# 08_-_MMC_SLOT.net
KiCad netlist of a schematic drawn in Altium Designer
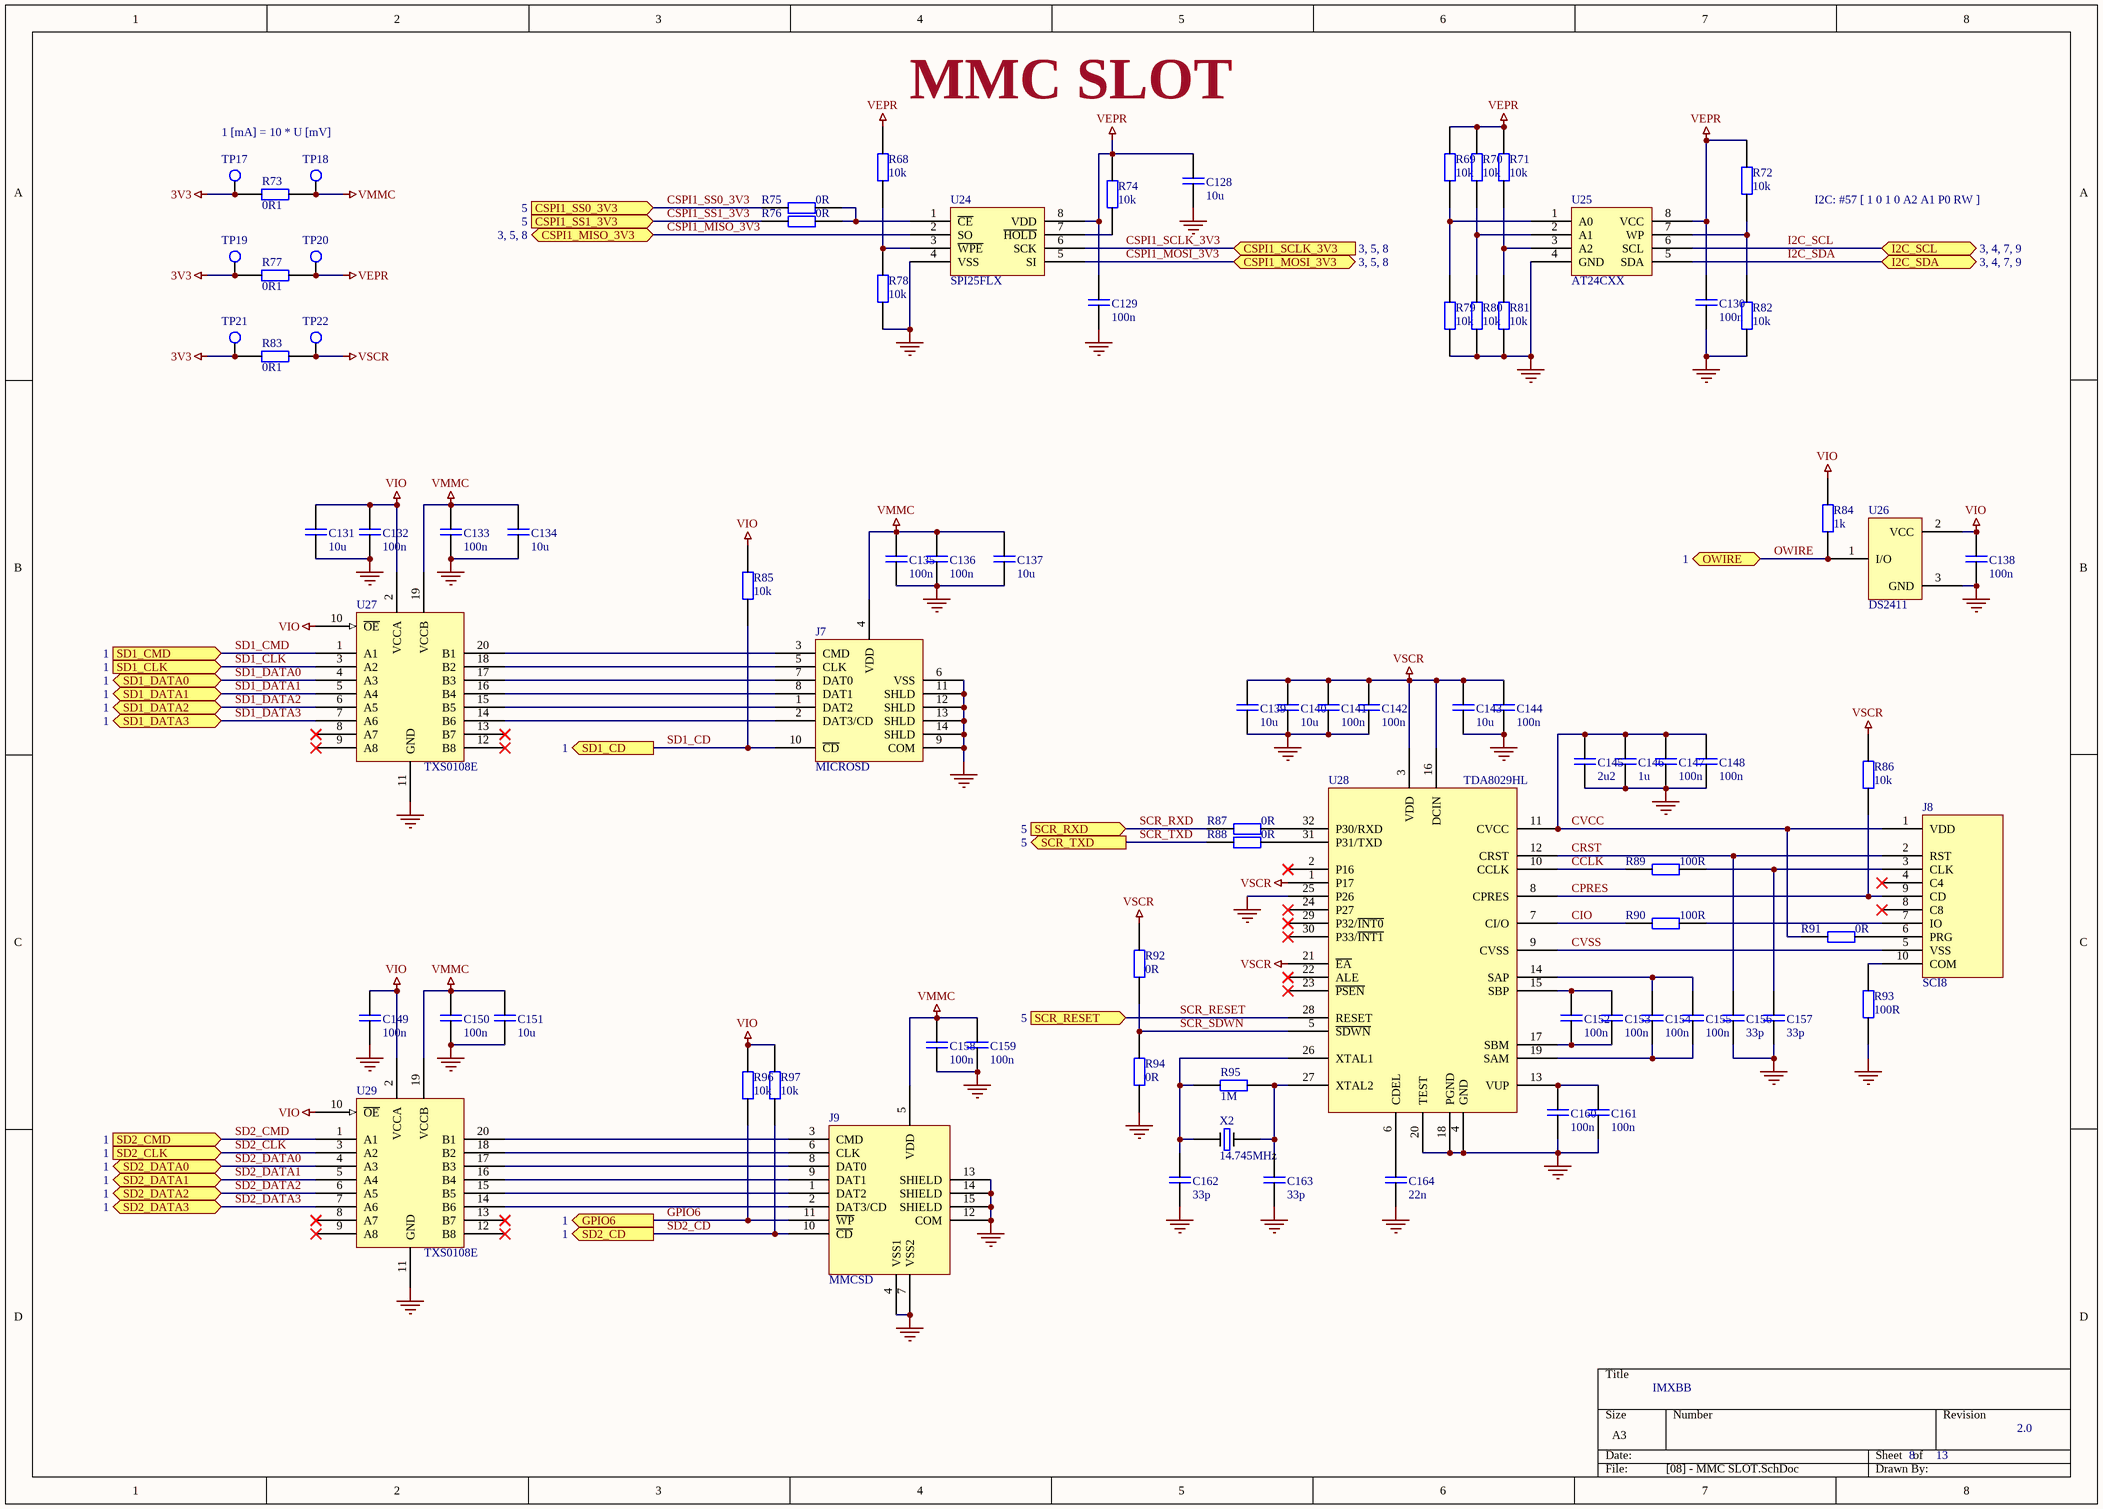
[diagram p0: [08] - MMC SLOT.SchDoc]

(export (version "E")
  (design (tool "Eeschema 10.0.6"))
  (components
    (comp (ref "C128") (value "10u") (footprint "0805") (libsource (lib "imxbb") (part "C")))
    (comp (ref "C129") (value "100n") (footprint "0603") (libsource (lib "imxbb") (part "C")))
    (comp (ref "C130") (value "100n") (footprint "0603") (libsource (lib "imxbb") (part "C")))
    (comp (ref "C131") (value "10u") (footprint "0805") (libsource (lib "imxbb") (part "C")))
    (comp (ref "C132") (value "100n") (footprint "0603") (libsource (lib "imxbb") (part "C")))
    (comp (ref "C133") (value "100n") (footprint "0603") (libsource (lib "imxbb") (part "C")))
    (comp (ref "C134") (value "10u") (footprint "0805") (libsource (lib "imxbb") (part "C")))
    (comp (ref "C135") (value "100n") (footprint "0603") (libsource (lib "imxbb") (part "C")))
    (comp (ref "C136") (value "100n") (footprint "0603") (libsource (lib "imxbb") (part "C")))
    (comp (ref "C137") (value "10u") (footprint "0805") (libsource (lib "imxbb") (part "C")))
    (comp (ref "C138") (value "100n") (footprint "0603") (libsource (lib "imxbb") (part "C")))
    (comp (ref "C139") (value "10u") (footprint "0805") (libsource (lib "imxbb") (part "C")))
    (comp (ref "C140") (value "10u") (footprint "0805") (libsource (lib "imxbb") (part "C")))
    (comp (ref "C141") (value "100n") (footprint "0603") (libsource (lib "imxbb") (part "C")))
    (comp (ref "C142") (value "100n") (footprint "0603") (libsource (lib "imxbb") (part "C")))
    (comp (ref "C143") (value "10u") (footprint "0805") (libsource (lib "imxbb") (part "C")))
    (comp (ref "C144") (value "100n") (footprint "0603") (libsource (lib "imxbb") (part "C")))
    (comp (ref "C145") (value "2u2") (footprint "0603") (libsource (lib "imxbb") (part "C")))
    (comp (ref "C146") (value "1u") (footprint "0603") (libsource (lib "imxbb") (part "C")))
    (comp (ref "C147") (value "100n") (footprint "0603") (libsource (lib "imxbb") (part "C")))
    (comp (ref "C148") (value "100n") (footprint "0603") (libsource (lib "imxbb") (part "C")))
    (comp (ref "C149") (value "100n") (footprint "0603") (libsource (lib "imxbb") (part "C")))
    (comp (ref "C150") (value "100n") (footprint "0603") (libsource (lib "imxbb") (part "C")))
    (comp (ref "C151") (value "10u") (footprint "0805") (libsource (lib "imxbb") (part "C")))
    (comp (ref "C152") (value "100n") (footprint "0603") (libsource (lib "imxbb") (part "C")))
    (comp (ref "C153") (value "100n") (footprint "0603") (libsource (lib "imxbb") (part "C")))
    (comp (ref "C154") (value "100n") (footprint "0603") (libsource (lib "imxbb") (part "C")))
    (comp (ref "C155") (value "100n") (footprint "0603") (libsource (lib "imxbb") (part "C")))
    (comp (ref "C156") (value "33p") (footprint "0603") (libsource (lib "imxbb") (part "C")))
    (comp (ref "C157") (value "33p") (footprint "0603") (libsource (lib "imxbb") (part "C")))
    (comp (ref "C158") (value "100n") (footprint "0603") (libsource (lib "imxbb") (part "C")))
    (comp (ref "C159") (value "100n") (footprint "0603") (libsource (lib "imxbb") (part "C")))
    (comp (ref "C160") (value "100n") (footprint "0603") (libsource (lib "imxbb") (part "C")))
    (comp (ref "C161") (value "100n") (footprint "0603") (libsource (lib "imxbb") (part "C")))
    (comp (ref "C162") (value "33p") (footprint "0603") (libsource (lib "imxbb") (part "C")))
    (comp (ref "C163") (value "33p") (footprint "0603") (libsource (lib "imxbb") (part "C")))
    (comp (ref "C164") (value "22n") (footprint "0603") (libsource (lib "imxbb") (part "C")))
    (comp (ref "J7") (value "MICROSD") (footprint "uSD10") (libsource (lib "imxbb") (part "MICROSD")))
    (comp (ref "J8") (value "SCI8") (footprint "SCI8F") (libsource (lib "imxbb") (part "SCI8")))
    (comp (ref "J9") (value "MMCSD") (footprint "SDCMF-109") (libsource (lib "imxbb") (part "MMCSD")))
    (comp (ref "R68") (value "10k") (footprint "0603") (libsource (lib "imxbb") (part "R")))
    (comp (ref "R69") (value "10k") (footprint "0603") (libsource (lib "imxbb") (part "R")))
    (comp (ref "R70") (value "10k") (footprint "0603") (libsource (lib "imxbb") (part "R")))
    (comp (ref "R71") (value "10k") (footprint "0603") (libsource (lib "imxbb") (part "R")))
    (comp (ref "R72") (value "10k") (footprint "0603") (libsource (lib "imxbb") (part "R")))
    (comp (ref "R73") (value "0R1") (footprint "0603") (libsource (lib "") (part "R_4")))
    (comp (ref "R74") (value "10k") (footprint "0603") (libsource (lib "imxbb") (part "R")))
    (comp (ref "R75") (value "0R") (footprint "0603") (libsource (lib "") (part "R_1")))
    (comp (ref "R76") (value "0R") (footprint "0603") (libsource (lib "") (part "R_1")))
    (comp (ref "R77") (value "0R1") (footprint "0603") (libsource (lib "") (part "R_4")))
    (comp (ref "R78") (value "10k") (footprint "0603") (libsource (lib "imxbb") (part "R")))
    (comp (ref "R79") (value "10k") (footprint "0603") (libsource (lib "imxbb") (part "R")))
    (comp (ref "R80") (value "10k") (footprint "0603") (libsource (lib "imxbb") (part "R")))
    (comp (ref "R81") (value "10k") (footprint "0603") (libsource (lib "imxbb") (part "R")))
    (comp (ref "R82") (value "10k") (footprint "0603") (libsource (lib "imxbb") (part "R")))
    (comp (ref "R83") (value "0R1") (footprint "0603") (libsource (lib "") (part "R_4")))
    (comp (ref "R84") (value "1k") (footprint "0603") (libsource (lib "imxbb") (part "R")))
    (comp (ref "R85") (value "10k") (footprint "0603") (libsource (lib "imxbb") (part "R")))
    (comp (ref "R86") (value "10k") (footprint "0603") (libsource (lib "") (part "R_3")))
    (comp (ref "R87") (value "0R") (footprint "0603") (libsource (lib "") (part "R_1")))
    (comp (ref "R88") (value "0R") (footprint "0603") (libsource (lib "") (part "R_1")))
    (comp (ref "R89") (value "100R") (footprint "0603") (libsource (lib "") (part "R_1")))
    (comp (ref "R90") (value "100R") (footprint "0603") (libsource (lib "") (part "R_1")))
    (comp (ref "R91") (value "0R") (footprint "0603") (libsource (lib "") (part "R_1")))
    (comp (ref "R92") (value "0R") (footprint "0603") (libsource (lib "") (part "R_3")))
    (comp (ref "R93") (value "100R") (footprint "0603") (libsource (lib "") (part "R_3")))
    (comp (ref "R94") (value "0R") (footprint "0603") (libsource (lib "") (part "R_3")))
    (comp (ref "R95") (value "1M") (footprint "0603") (libsource (lib "") (part "R_2")))
    (comp (ref "R96") (value "10k") (footprint "0603") (libsource (lib "imxbb") (part "R")))
    (comp (ref "R97") (value "10k") (footprint "0603") (libsource (lib "imxbb") (part "R")))
    (comp (ref "TP17")
      (value "TESTPOINT")
      (footprint "TESTPOINT_2mm")
      (description "Testpoint pad")
      (libsource (lib "imxbb") (part "TESTPOINT"))
    )
    (comp (ref "TP18")
      (value "TESTPOINT")
      (footprint "TESTPOINT_2mm")
      (description "Testpoint pad")
      (libsource (lib "imxbb") (part "TESTPOINT"))
    )
    (comp (ref "TP19")
      (value "TESTPOINT")
      (footprint "TESTPOINT_2mm")
      (description "Testpoint pad")
      (libsource (lib "imxbb") (part "TESTPOINT"))
    )
    (comp (ref "TP20")
      (value "TESTPOINT")
      (footprint "TESTPOINT_2mm")
      (description "Testpoint pad")
      (libsource (lib "imxbb") (part "TESTPOINT"))
    )
    (comp (ref "TP21")
      (value "TESTPOINT")
      (footprint "TESTPOINT_2mm")
      (description "Testpoint pad")
      (libsource (lib "imxbb") (part "TESTPOINT"))
    )
    (comp (ref "TP22")
      (value "TESTPOINT")
      (footprint "TESTPOINT_2mm")
      (description "Testpoint pad")
      (libsource (lib "imxbb") (part "TESTPOINT"))
    )
    (comp (ref "U24") (value "SPI25FLX") (footprint "SOIC8") (libsource (lib "imxbb") (part "SPI25FLX")))
    (comp (ref "U25") (value "AT24CXX") (footprint "SOIC8") (libsource (lib "imxbb") (part "AT24CXX")))
    (comp (ref "U26") (value "DS2411") (footprint "SOT23") (libsource (lib "imxbb") (part "DS2411")))
    (comp (ref "U27") (value "TXS0108E") (footprint "TSSOP20") (libsource (lib "imxbb") (part "TXS0108E")))
    (comp (ref "U28") (value "TDA8029HL") (footprint "LQFP32") (libsource (lib "imxbb") (part "TDA8029HL")))
    (comp (ref "U29") (value "TXS0108E") (footprint "TSSOP20") (libsource (lib "imxbb") (part "TXS0108E")))
    (comp (ref "X2") (value "14.745MHz") (footprint "HC494H") (libsource (lib "imxbb") (part "XTAL")))
  )
  (nets
    (net (code "1") (name "/CCLK") (class "Default")
      (node (ref "R89") (pin "1") (pinfunction "1_1") (pintype "passive"))
      (node (ref "U28") (pin "10") (pinfunction "CCLK_10") (pintype "passive"))
    )
    (net (code "2") (name "/CIO") (class "Default")
      (node (ref "R90") (pin "1") (pinfunction "1_1") (pintype "passive"))
      (node (ref "U28") (pin "7") (pinfunction "CI/O_7") (pintype "passive"))
    )
    (net (code "3") (name "/CPRES") (class "Default")
      (node (ref "J8") (pin "9") (pinfunction "CD_9") (pintype "passive"))
      (node (ref "R86") (pin "1") (pinfunction "1_1") (pintype "passive"))
      (node (ref "U28") (pin "8") (pinfunction "CPRES_8") (pintype "passive"))
    )
    (net (code "4") (name "/CRST") (class "Default")
      (node (ref "C156") (pin "2") (pinfunction "2_2") (pintype "passive"))
      (node (ref "J8") (pin "2") (pinfunction "RST_2") (pintype "passive"))
      (node (ref "U28") (pin "12") (pinfunction "CRST_12") (pintype "passive"))
    )
    (net (code "5") (name "/CSPI1_MISO_3V3") (class "Default")
      (node (ref "U24") (pin "2") (pinfunction "SO_2") (pintype "passive"))
    )
    (net (code "6") (name "/CSPI1_MOSI_3V3") (class "Default")
      (node (ref "U24") (pin "5") (pinfunction "SI_5") (pintype "passive"))
    )
    (net (code "7") (name "/CSPI1_SCLK_3V3") (class "Default")
      (node (ref "U24") (pin "6") (pinfunction "SCK_6") (pintype "passive"))
    )
    (net (code "8") (name "/CSPI1_SS0_3V3") (class "Default")
      (node (ref "R75") (pin "1") (pinfunction "1_1") (pintype "passive"))
    )
    (net (code "9") (name "/CSPI1_SS1_3V3") (class "Default")
      (node (ref "R76") (pin "1") (pinfunction "1_1") (pintype "passive"))
    )
    (net (code "10") (name "/CVCC") (class "Default")
      (node (ref "C145") (pin "2") (pinfunction "2_2") (pintype "passive"))
      (node (ref "C146") (pin "2") (pinfunction "2_2") (pintype "passive"))
      (node (ref "C147") (pin "2") (pinfunction "2_2") (pintype "passive"))
      (node (ref "C148") (pin "2") (pinfunction "2_2") (pintype "passive"))
      (node (ref "J8") (pin "1") (pinfunction "VDD_1") (pintype "passive"))
      (node (ref "R91") (pin "1") (pinfunction "1_1") (pintype "passive"))
      (node (ref "U28") (pin "11") (pinfunction "CVCC_11") (pintype "passive"))
    )
    (net (code "11") (name "/CVSS") (class "Default")
      (node (ref "J8") (pin "5") (pinfunction "VSS_5") (pintype "passive"))
      (node (ref "U28") (pin "9") (pinfunction "CVSS_9") (pintype "passive"))
    )
    (net (code "12") (name "/GPIO6") (class "Default")
      (node (ref "J9") (pin "11") (pinfunction "~{WP}_11") (pintype "passive"))
      (node (ref "R96") (pin "2") (pinfunction "2_2") (pintype "passive"))
    )
    (net (code "13") (name "/I2C_SCL") (class "Default")
      (node (ref "U25") (pin "6") (pinfunction "SCL_6") (pintype "passive"))
    )
    (net (code "14") (name "/I2C_SDA") (class "Default")
      (node (ref "U25") (pin "5") (pinfunction "SDA_5") (pintype "passive"))
    )
    (net (code "15") (name "/OWIRE") (class "Default")
      (node (ref "R84") (pin "2") (pinfunction "2_2") (pintype "passive"))
      (node (ref "U26") (pin "1") (pinfunction "I/O_1") (pintype "passive"))
    )
    (net (code "16") (name "/SCR_RESET") (class "Default")
      (node (ref "U28") (pin "28") (pinfunction "RESET_28") (pintype "passive"))
    )
    (net (code "17") (name "/SCR_RXD") (class "Default")
      (node (ref "R87") (pin "1") (pinfunction "1_1") (pintype "passive"))
    )
    (net (code "18") (name "/SCR_SDWN") (class "Default")
      (node (ref "R92") (pin "1") (pinfunction "1_1") (pintype "passive"))
      (node (ref "R94") (pin "2") (pinfunction "2_2") (pintype "passive"))
      (node (ref "U28") (pin "5") (pinfunction "~{SDWN}_5") (pintype "passive"))
    )
    (net (code "19") (name "/SCR_TXD") (class "Default")
      (node (ref "R88") (pin "1") (pinfunction "1_1") (pintype "passive"))
    )
    (net (code "20") (name "/SD1_CD") (class "Default")
      (node (ref "J7") (pin "10") (pinfunction "~{CD}_10") (pintype "passive"))
      (node (ref "R85") (pin "2") (pinfunction "2_2") (pintype "passive"))
    )
    (net (code "21") (name "/SD1_CLK") (class "Default")
      (node (ref "U27") (pin "3") (pinfunction "A2_3") (pintype "passive"))
    )
    (net (code "22") (name "/SD1_CMD") (class "Default")
      (node (ref "U27") (pin "1") (pinfunction "A1_1") (pintype "passive"))
    )
    (net (code "23") (name "/SD1_DATA0") (class "Default")
      (node (ref "U27") (pin "4") (pinfunction "A3_4") (pintype "passive"))
    )
    (net (code "24") (name "/SD1_DATA1") (class "Default")
      (node (ref "U27") (pin "5") (pinfunction "A4_5") (pintype "passive"))
    )
    (net (code "25") (name "/SD1_DATA2") (class "Default")
      (node (ref "U27") (pin "6") (pinfunction "A5_6") (pintype "passive"))
    )
    (net (code "26") (name "/SD1_DATA3") (class "Default")
      (node (ref "U27") (pin "7") (pinfunction "A6_7") (pintype "passive"))
    )
    (net (code "27") (name "/SD2_CD") (class "Default")
      (node (ref "J9") (pin "10") (pinfunction "~{CD}_10") (pintype "passive"))
      (node (ref "R97") (pin "2") (pinfunction "2_2") (pintype "passive"))
    )
    (net (code "28") (name "/SD2_CLK") (class "Default")
      (node (ref "U29") (pin "3") (pinfunction "A2_3") (pintype "passive"))
    )
    (net (code "29") (name "/SD2_CMD") (class "Default")
      (node (ref "U29") (pin "1") (pinfunction "A1_1") (pintype "passive"))
    )
    (net (code "30") (name "/SD2_DATA0") (class "Default")
      (node (ref "U29") (pin "4") (pinfunction "A3_4") (pintype "passive"))
    )
    (net (code "31") (name "/SD2_DATA1") (class "Default")
      (node (ref "U29") (pin "5") (pinfunction "A4_5") (pintype "passive"))
    )
    (net (code "32") (name "/SD2_DATA2") (class "Default")
      (node (ref "U29") (pin "6") (pinfunction "A5_6") (pintype "passive"))
    )
    (net (code "33") (name "/SD2_DATA3") (class "Default")
      (node (ref "U29") (pin "7") (pinfunction "A6_7") (pintype "passive"))
    )
    (net (code "34") (name "3V3") (class "Default")
      (node (ref "R73") (pin "1") (pinfunction "1_1") (pintype "passive"))
      (node (ref "R77") (pin "1") (pinfunction "1_1") (pintype "passive"))
      (node (ref "R83") (pin "1") (pinfunction "1_1") (pintype "passive"))
      (node (ref "TP17") (pin "1") (pinfunction "1_1") (pintype "passive"))
      (node (ref "TP19") (pin "1") (pinfunction "1_1") (pintype "passive"))
      (node (ref "TP21") (pin "1") (pinfunction "1_1") (pintype "passive"))
    )
    (net (code "35") (name "GND") (class "Default")
      (node (ref "C128") (pin "1") (pinfunction "1_1") (pintype "passive"))
      (node (ref "C129") (pin "1") (pinfunction "1_1") (pintype "passive"))
      (node (ref "C130") (pin "1") (pinfunction "1_1") (pintype "passive"))
      (node (ref "C131") (pin "1") (pinfunction "1_1") (pintype "passive"))
      (node (ref "C132") (pin "1") (pinfunction "1_1") (pintype "passive"))
      (node (ref "C133") (pin "1") (pinfunction "1_1") (pintype "passive"))
      (node (ref "C134") (pin "1") (pinfunction "1_1") (pintype "passive"))
      (node (ref "C135") (pin "1") (pinfunction "1_1") (pintype "passive"))
      (node (ref "C136") (pin "1") (pinfunction "1_1") (pintype "passive"))
      (node (ref "C137") (pin "1") (pinfunction "1_1") (pintype "passive"))
      (node (ref "C138") (pin "1") (pinfunction "1_1") (pintype "passive"))
      (node (ref "C139") (pin "1") (pinfunction "1_1") (pintype "passive"))
      (node (ref "C140") (pin "1") (pinfunction "1_1") (pintype "passive"))
      (node (ref "C141") (pin "1") (pinfunction "1_1") (pintype "passive"))
      (node (ref "C142") (pin "1") (pinfunction "1_1") (pintype "passive"))
      (node (ref "C143") (pin "1") (pinfunction "1_1") (pintype "passive"))
      (node (ref "C144") (pin "1") (pinfunction "1_1") (pintype "passive"))
      (node (ref "C145") (pin "1") (pinfunction "1_1") (pintype "passive"))
      (node (ref "C146") (pin "1") (pinfunction "1_1") (pintype "passive"))
      (node (ref "C147") (pin "1") (pinfunction "1_1") (pintype "passive"))
      (node (ref "C148") (pin "1") (pinfunction "1_1") (pintype "passive"))
      (node (ref "C149") (pin "1") (pinfunction "1_1") (pintype "passive"))
      (node (ref "C150") (pin "1") (pinfunction "1_1") (pintype "passive"))
      (node (ref "C151") (pin "1") (pinfunction "1_1") (pintype "passive"))
      (node (ref "C156") (pin "1") (pinfunction "1_1") (pintype "passive"))
      (node (ref "C157") (pin "1") (pinfunction "1_1") (pintype "passive"))
      (node (ref "C158") (pin "1") (pinfunction "1_1") (pintype "passive"))
      (node (ref "C159") (pin "1") (pinfunction "1_1") (pintype "passive"))
      (node (ref "C160") (pin "1") (pinfunction "1_1") (pintype "passive"))
      (node (ref "C161") (pin "1") (pinfunction "1_1") (pintype "passive"))
      (node (ref "C162") (pin "1") (pinfunction "1_1") (pintype "passive"))
      (node (ref "C163") (pin "1") (pinfunction "1_1") (pintype "passive"))
      (node (ref "C164") (pin "1") (pinfunction "1_1") (pintype "passive"))
      (node (ref "J7") (pin "11") (pinfunction "SHLD_11") (pintype "passive"))
      (node (ref "J7") (pin "12") (pinfunction "SHLD_12") (pintype "passive"))
      (node (ref "J7") (pin "13") (pinfunction "SHLD_13") (pintype "passive"))
      (node (ref "J7") (pin "14") (pinfunction "SHLD_14") (pintype "passive"))
      (node (ref "J7") (pin "6") (pinfunction "VSS_6") (pintype "passive"))
      (node (ref "J7") (pin "9") (pinfunction "COM_9") (pintype "passive"))
      (node (ref "J9") (pin "12") (pinfunction "COM_12") (pintype "passive"))
      (node (ref "J9") (pin "13") (pinfunction "SHIELD_13") (pintype "passive"))
      (node (ref "J9") (pin "14") (pinfunction "SHIELD_14") (pintype "passive"))
      (node (ref "J9") (pin "15") (pinfunction "SHIELD_15") (pintype "passive"))
      (node (ref "J9") (pin "4") (pinfunction "VSS1_4") (pintype "passive"))
      (node (ref "J9") (pin "7") (pinfunction "VSS2_7") (pintype "passive"))
      (node (ref "R78") (pin "2") (pinfunction "2_2") (pintype "passive"))
      (node (ref "R79") (pin "2") (pinfunction "2_2") (pintype "passive"))
      (node (ref "R80") (pin "2") (pinfunction "2_2") (pintype "passive"))
      (node (ref "R81") (pin "2") (pinfunction "2_2") (pintype "passive"))
      (node (ref "R82") (pin "2") (pinfunction "2_2") (pintype "passive"))
      (node (ref "R93") (pin "1") (pinfunction "1_1") (pintype "passive"))
      (node (ref "R94") (pin "1") (pinfunction "1_1") (pintype "passive"))
      (node (ref "U24") (pin "4") (pinfunction "VSS_4") (pintype "passive"))
      (node (ref "U25") (pin "4") (pinfunction "GND_4") (pintype "passive"))
      (node (ref "U26") (pin "3") (pinfunction "GND_3") (pintype "passive"))
      (node (ref "U27") (pin "11") (pinfunction "GND_11") (pintype "power_in"))
      (node (ref "U28") (pin "18") (pinfunction "PGND_18") (pintype "passive"))
      (node (ref "U28") (pin "20") (pinfunction "TEST_20") (pintype "passive"))
      (node (ref "U28") (pin "25") (pinfunction "P26_25") (pintype "passive"))
      (node (ref "U28") (pin "4") (pinfunction "GND_4") (pintype "passive"))
      (node (ref "U29") (pin "11") (pinfunction "GND_11") (pintype "power_in"))
    )
    (net (code "36") (name "Net-(J7-CLK)") (class "Default")
      (node (ref "J7") (pin "5") (pinfunction "CLK_5") (pintype "passive"))
      (node (ref "U27") (pin "18") (pinfunction "B2_18") (pintype "passive"))
    )
    (net (code "37") (name "Net-(J7-CMD)") (class "Default")
      (node (ref "J7") (pin "3") (pinfunction "CMD_3") (pintype "passive"))
      (node (ref "U27") (pin "20") (pinfunction "B1_20") (pintype "passive"))
    )
    (net (code "38") (name "Net-(J7-DAT0)") (class "Default")
      (node (ref "J7") (pin "7") (pinfunction "DAT0_7") (pintype "passive"))
      (node (ref "U27") (pin "17") (pinfunction "B3_17") (pintype "passive"))
    )
    (net (code "39") (name "Net-(J7-DAT1)") (class "Default")
      (node (ref "J7") (pin "8") (pinfunction "DAT1_8") (pintype "passive"))
      (node (ref "U27") (pin "16") (pinfunction "B4_16") (pintype "passive"))
    )
    (net (code "40") (name "Net-(J7-DAT2)") (class "Default")
      (node (ref "J7") (pin "1") (pinfunction "DAT2_1") (pintype "passive"))
      (node (ref "U27") (pin "15") (pinfunction "B5_15") (pintype "passive"))
    )
    (net (code "41") (name "Net-(J7-DAT3{slash}CD)") (class "Default")
      (node (ref "J7") (pin "2") (pinfunction "DAT3/CD_2") (pintype "passive"))
      (node (ref "U27") (pin "14") (pinfunction "B6_14") (pintype "passive"))
    )
    (net (code "42") (name "Net-(J8-CLK)") (class "Default")
      (node (ref "C157") (pin "2") (pinfunction "2_2") (pintype "passive"))
      (node (ref "J8") (pin "3") (pinfunction "CLK_3") (pintype "passive"))
      (node (ref "R89") (pin "2") (pinfunction "2_2") (pintype "passive"))
    )
    (net (code "43") (name "Net-(J8-COM)") (class "Default")
      (node (ref "J8") (pin "10") (pinfunction "COM_10") (pintype "passive"))
      (node (ref "R93") (pin "2") (pinfunction "2_2") (pintype "passive"))
    )
    (net (code "44") (name "Net-(J8-IO)") (class "Default")
      (node (ref "J8") (pin "7") (pinfunction "IO_7") (pintype "passive"))
      (node (ref "R90") (pin "2") (pinfunction "2_2") (pintype "passive"))
    )
    (net (code "45") (name "Net-(J8-PRG)") (class "Default")
      (node (ref "J8") (pin "6") (pinfunction "PRG_6") (pintype "passive"))
      (node (ref "R91") (pin "2") (pinfunction "2_2") (pintype "passive"))
    )
    (net (code "46") (name "Net-(J9-CLK)") (class "Default")
      (node (ref "J9") (pin "6") (pinfunction "CLK_6") (pintype "passive"))
      (node (ref "U29") (pin "18") (pinfunction "B2_18") (pintype "passive"))
    )
    (net (code "47") (name "Net-(J9-CMD)") (class "Default")
      (node (ref "J9") (pin "3") (pinfunction "CMD_3") (pintype "passive"))
      (node (ref "U29") (pin "20") (pinfunction "B1_20") (pintype "passive"))
    )
    (net (code "48") (name "Net-(J9-DAT0)") (class "Default")
      (node (ref "J9") (pin "8") (pinfunction "DAT0_8") (pintype "passive"))
      (node (ref "U29") (pin "17") (pinfunction "B3_17") (pintype "passive"))
    )
    (net (code "49") (name "Net-(J9-DAT1)") (class "Default")
      (node (ref "J9") (pin "9") (pinfunction "DAT1_9") (pintype "passive"))
      (node (ref "U29") (pin "16") (pinfunction "B4_16") (pintype "passive"))
    )
    (net (code "50") (name "Net-(J9-DAT2)") (class "Default")
      (node (ref "J9") (pin "1") (pinfunction "DAT2_1") (pintype "passive"))
      (node (ref "U29") (pin "15") (pinfunction "B5_15") (pintype "passive"))
    )
    (net (code "51") (name "Net-(J9-DAT3{slash}CD)") (class "Default")
      (node (ref "J9") (pin "2") (pinfunction "DAT3/CD_2") (pintype "passive"))
      (node (ref "U29") (pin "14") (pinfunction "B6_14") (pintype "passive"))
    )
    (net (code "52") (name "Net-(U24-~{CE})") (class "Default")
      (node (ref "R75") (pin "2") (pinfunction "2_2") (pintype "passive"))
      (node (ref "R76") (pin "2") (pinfunction "2_2") (pintype "passive"))
      (node (ref "U24") (pin "1") (pinfunction "~{CE}_1") (pintype "passive"))
    )
    (net (code "53") (name "Net-(U24-~{HOLD})") (class "Default")
      (node (ref "R74") (pin "2") (pinfunction "2_2") (pintype "passive"))
      (node (ref "U24") (pin "7") (pinfunction "~{HOLD}_7") (pintype "passive"))
    )
    (net (code "54") (name "Net-(U24-~{WPE})") (class "Default")
      (node (ref "R68") (pin "2") (pinfunction "2_2") (pintype "passive"))
      (node (ref "R78") (pin "1") (pinfunction "1_1") (pintype "passive"))
      (node (ref "U24") (pin "3") (pinfunction "~{WPE}_3") (pintype "passive"))
    )
    (net (code "55") (name "Net-(U25-A0)") (class "Default")
      (node (ref "R69") (pin "2") (pinfunction "2_2") (pintype "passive"))
      (node (ref "R79") (pin "1") (pinfunction "1_1") (pintype "passive"))
      (node (ref "U25") (pin "1") (pinfunction "A0_1") (pintype "passive"))
    )
    (net (code "56") (name "Net-(U25-A1)") (class "Default")
      (node (ref "R70") (pin "2") (pinfunction "2_2") (pintype "passive"))
      (node (ref "R80") (pin "1") (pinfunction "1_1") (pintype "passive"))
      (node (ref "U25") (pin "2") (pinfunction "A1_2") (pintype "passive"))
    )
    (net (code "57") (name "Net-(U25-A2)") (class "Default")
      (node (ref "R71") (pin "2") (pinfunction "2_2") (pintype "passive"))
      (node (ref "R81") (pin "1") (pinfunction "1_1") (pintype "passive"))
      (node (ref "U25") (pin "3") (pinfunction "A2_3") (pintype "passive"))
    )
    (net (code "58") (name "Net-(U25-WP)") (class "Default")
      (node (ref "R72") (pin "2") (pinfunction "2_2") (pintype "passive"))
      (node (ref "R82") (pin "1") (pinfunction "1_1") (pintype "passive"))
      (node (ref "U25") (pin "7") (pinfunction "WP_7") (pintype "passive"))
    )
    (net (code "59") (name "Net-(U28-CDEL)") (class "Default")
      (node (ref "C164") (pin "2") (pinfunction "2_2") (pintype "passive"))
      (node (ref "U28") (pin "6") (pinfunction "CDEL_6") (pintype "passive"))
    )
    (net (code "60") (name "Net-(U28-P30{slash}RXD)") (class "Default")
      (node (ref "R87") (pin "2") (pinfunction "2_2") (pintype "passive"))
      (node (ref "U28") (pin "32") (pinfunction "P30/RXD_32") (pintype "passive"))
    )
    (net (code "61") (name "Net-(U28-P31{slash}TXD)") (class "Default")
      (node (ref "R88") (pin "2") (pinfunction "2_2") (pintype "passive"))
      (node (ref "U28") (pin "31") (pinfunction "P31/TXD_31") (pintype "passive"))
    )
    (net (code "62") (name "Net-(U28-SAM)") (class "Default")
      (node (ref "C154") (pin "1") (pinfunction "1_1") (pintype "passive"))
      (node (ref "C155") (pin "1") (pinfunction "1_1") (pintype "passive"))
      (node (ref "U28") (pin "19") (pinfunction "SAM_19") (pintype "passive"))
    )
    (net (code "63") (name "Net-(U28-SAP)") (class "Default")
      (node (ref "C154") (pin "2") (pinfunction "2_2") (pintype "passive"))
      (node (ref "C155") (pin "2") (pinfunction "2_2") (pintype "passive"))
      (node (ref "U28") (pin "14") (pinfunction "SAP_14") (pintype "passive"))
    )
    (net (code "64") (name "Net-(U28-SBM)") (class "Default")
      (node (ref "C152") (pin "1") (pinfunction "1_1") (pintype "passive"))
      (node (ref "C153") (pin "1") (pinfunction "1_1") (pintype "passive"))
      (node (ref "U28") (pin "17") (pinfunction "SBM_17") (pintype "passive"))
    )
    (net (code "65") (name "Net-(U28-SBP)") (class "Default")
      (node (ref "C152") (pin "2") (pinfunction "2_2") (pintype "passive"))
      (node (ref "C153") (pin "2") (pinfunction "2_2") (pintype "passive"))
      (node (ref "U28") (pin "15") (pinfunction "SBP_15") (pintype "passive"))
    )
    (net (code "66") (name "Net-(U28-VUP)") (class "Default")
      (node (ref "C160") (pin "2") (pinfunction "2_2") (pintype "passive"))
      (node (ref "C161") (pin "2") (pinfunction "2_2") (pintype "passive"))
      (node (ref "U28") (pin "13") (pinfunction "VUP_13") (pintype "passive"))
    )
    (net (code "67") (name "Net-(U28-XTAL1)") (class "Default")
      (node (ref "C162") (pin "2") (pinfunction "2_2") (pintype "passive"))
      (node (ref "R95") (pin "2") (pinfunction "2_2") (pintype "passive"))
      (node (ref "U28") (pin "26") (pinfunction "XTAL1_26") (pintype "passive"))
      (node (ref "X2") (pin "1") (pinfunction "1_1") (pintype "passive"))
    )
    (net (code "68") (name "Net-(U28-XTAL2)") (class "Default")
      (node (ref "C163") (pin "2") (pinfunction "2_2") (pintype "passive"))
      (node (ref "R95") (pin "1") (pinfunction "1_1") (pintype "passive"))
      (node (ref "U28") (pin "27") (pinfunction "XTAL2_27") (pintype "passive"))
      (node (ref "X2") (pin "2") (pinfunction "2_2") (pintype "passive"))
    )
    (net (code "69") (name "VEPR") (class "Default")
      (node (ref "C128") (pin "2") (pinfunction "2_2") (pintype "passive"))
      (node (ref "C129") (pin "2") (pinfunction "2_2") (pintype "passive"))
      (node (ref "C130") (pin "2") (pinfunction "2_2") (pintype "passive"))
      (node (ref "R68") (pin "1") (pinfunction "1_1") (pintype "passive"))
      (node (ref "R69") (pin "1") (pinfunction "1_1") (pintype "passive"))
      (node (ref "R70") (pin "1") (pinfunction "1_1") (pintype "passive"))
      (node (ref "R71") (pin "1") (pinfunction "1_1") (pintype "passive"))
      (node (ref "R72") (pin "1") (pinfunction "1_1") (pintype "passive"))
      (node (ref "R74") (pin "1") (pinfunction "1_1") (pintype "passive"))
      (node (ref "R77") (pin "2") (pinfunction "2_2") (pintype "passive"))
      (node (ref "TP20") (pin "1") (pinfunction "1_1") (pintype "passive"))
      (node (ref "U24") (pin "8") (pinfunction "VDD_8") (pintype "passive"))
      (node (ref "U25") (pin "8") (pinfunction "VCC_8") (pintype "passive"))
    )
    (net (code "70") (name "VIO") (class "Default")
      (node (ref "C131") (pin "2") (pinfunction "2_2") (pintype "passive"))
      (node (ref "C132") (pin "2") (pinfunction "2_2") (pintype "passive"))
      (node (ref "C138") (pin "2") (pinfunction "2_2") (pintype "passive"))
      (node (ref "C149") (pin "2") (pinfunction "2_2") (pintype "passive"))
      (node (ref "R84") (pin "1") (pinfunction "1_1") (pintype "passive"))
      (node (ref "R85") (pin "1") (pinfunction "1_1") (pintype "passive"))
      (node (ref "R96") (pin "1") (pinfunction "1_1") (pintype "passive"))
      (node (ref "R97") (pin "1") (pinfunction "1_1") (pintype "passive"))
      (node (ref "U26") (pin "2") (pinfunction "VCC_2") (pintype "passive"))
      (node (ref "U27") (pin "10") (pinfunction "~{OE}_10") (pintype "input"))
      (node (ref "U27") (pin "2") (pinfunction "VCCA_2") (pintype "power_in"))
      (node (ref "U29") (pin "10") (pinfunction "~{OE}_10") (pintype "input"))
      (node (ref "U29") (pin "2") (pinfunction "VCCA_2") (pintype "power_in"))
    )
    (net (code "71") (name "VMMC") (class "Default")
      (node (ref "C133") (pin "2") (pinfunction "2_2") (pintype "passive"))
      (node (ref "C134") (pin "2") (pinfunction "2_2") (pintype "passive"))
      (node (ref "C135") (pin "2") (pinfunction "2_2") (pintype "passive"))
      (node (ref "C136") (pin "2") (pinfunction "2_2") (pintype "passive"))
      (node (ref "C137") (pin "2") (pinfunction "2_2") (pintype "passive"))
      (node (ref "C150") (pin "2") (pinfunction "2_2") (pintype "passive"))
      (node (ref "C151") (pin "2") (pinfunction "2_2") (pintype "passive"))
      (node (ref "C158") (pin "2") (pinfunction "2_2") (pintype "passive"))
      (node (ref "C159") (pin "2") (pinfunction "2_2") (pintype "passive"))
      (node (ref "J7") (pin "4") (pinfunction "VDD_4") (pintype "passive"))
      (node (ref "J9") (pin "5") (pinfunction "VDD_5") (pintype "passive"))
      (node (ref "R73") (pin "2") (pinfunction "2_2") (pintype "passive"))
      (node (ref "TP18") (pin "1") (pinfunction "1_1") (pintype "passive"))
      (node (ref "U27") (pin "19") (pinfunction "VCCB_19") (pintype "power_in"))
      (node (ref "U29") (pin "19") (pinfunction "VCCB_19") (pintype "power_in"))
    )
    (net (code "72") (name "VSCR") (class "Default")
      (node (ref "C139") (pin "2") (pinfunction "2_2") (pintype "passive"))
      (node (ref "C140") (pin "2") (pinfunction "2_2") (pintype "passive"))
      (node (ref "C141") (pin "2") (pinfunction "2_2") (pintype "passive"))
      (node (ref "C142") (pin "2") (pinfunction "2_2") (pintype "passive"))
      (node (ref "C143") (pin "2") (pinfunction "2_2") (pintype "passive"))
      (node (ref "C144") (pin "2") (pinfunction "2_2") (pintype "passive"))
      (node (ref "R83") (pin "2") (pinfunction "2_2") (pintype "passive"))
      (node (ref "R86") (pin "2") (pinfunction "2_2") (pintype "passive"))
      (node (ref "R92") (pin "2") (pinfunction "2_2") (pintype "passive"))
      (node (ref "TP22") (pin "1") (pinfunction "1_1") (pintype "passive"))
      (node (ref "U28") (pin "1") (pinfunction "P17_1") (pintype "passive"))
      (node (ref "U28") (pin "16") (pinfunction "DCIN_16") (pintype "passive"))
      (node (ref "U28") (pin "21") (pinfunction "~{EA}_21") (pintype "passive"))
      (node (ref "U28") (pin "3") (pinfunction "VDD_3") (pintype "passive"))
    )
    (net (code "73") (name "unconnected-(J8-C4-Pad4)") (class "Default")
      (node (ref "J8") (pin "4") (pinfunction "C4_4") (pintype "passive+no_connect"))
    )
    (net (code "74") (name "unconnected-(J8-C8-Pad8)") (class "Default")
      (node (ref "J8") (pin "8") (pinfunction "C8_8") (pintype "passive+no_connect"))
    )
    (net (code "75") (name "unconnected-(U27-A7-Pad8)") (class "Default")
      (node (ref "U27") (pin "8") (pinfunction "A7_8") (pintype "passive+no_connect"))
    )
    (net (code "76") (name "unconnected-(U27-A8-Pad9)") (class "Default")
      (node (ref "U27") (pin "9") (pinfunction "A8_9") (pintype "passive+no_connect"))
    )
    (net (code "77") (name "unconnected-(U27-B7-Pad13)") (class "Default")
      (node (ref "U27") (pin "13") (pinfunction "B7_13") (pintype "passive+no_connect"))
    )
    (net (code "78") (name "unconnected-(U27-B8-Pad12)") (class "Default")
      (node (ref "U27") (pin "12") (pinfunction "B8_12") (pintype "passive+no_connect"))
    )
    (net (code "79") (name "unconnected-(U28-ALE-Pad22)") (class "Default")
      (node (ref "U28") (pin "22") (pinfunction "ALE_22") (pintype "passive+no_connect"))
    )
    (net (code "80") (name "unconnected-(U28-P16-Pad2)") (class "Default")
      (node (ref "U28") (pin "2") (pinfunction "P16_2") (pintype "passive+no_connect"))
    )
    (net (code "81") (name "unconnected-(U28-P27-Pad24)") (class "Default")
      (node (ref "U28") (pin "24") (pinfunction "P27_24") (pintype "passive+no_connect"))
    )
    (net (code "82") (name "unconnected-(U28-P32{slash}~{INT0}-Pad29)") (class "Default")
      (node (ref "U28") (pin "29") (pinfunction "P32/~{INT0}_29") (pintype "passive+no_connect"))
    )
    (net (code "83") (name "unconnected-(U28-P33{slash}~{INT1}-Pad30)") (class "Default")
      (node (ref "U28") (pin "30") (pinfunction "P33/~{INT1}_30") (pintype "passive+no_connect"))
    )
    (net (code "84") (name "unconnected-(U28-~{PSEN}-Pad23)") (class "Default")
      (node (ref "U28") (pin "23") (pinfunction "~{PSEN}_23") (pintype "passive+no_connect"))
    )
    (net (code "85") (name "unconnected-(U29-A7-Pad8)") (class "Default")
      (node (ref "U29") (pin "8") (pinfunction "A7_8") (pintype "passive+no_connect"))
    )
    (net (code "86") (name "unconnected-(U29-A8-Pad9)") (class "Default")
      (node (ref "U29") (pin "9") (pinfunction "A8_9") (pintype "passive+no_connect"))
    )
    (net (code "87") (name "unconnected-(U29-B7-Pad13)") (class "Default")
      (node (ref "U29") (pin "13") (pinfunction "B7_13") (pintype "passive+no_connect"))
    )
    (net (code "88") (name "unconnected-(U29-B8-Pad12)") (class "Default")
      (node (ref "U29") (pin "12") (pinfunction "B8_12") (pintype "passive+no_connect"))
    )
  )
)
